# Virtual_Boy.net
KiCad netlist of a schematic drawn in EAGLE
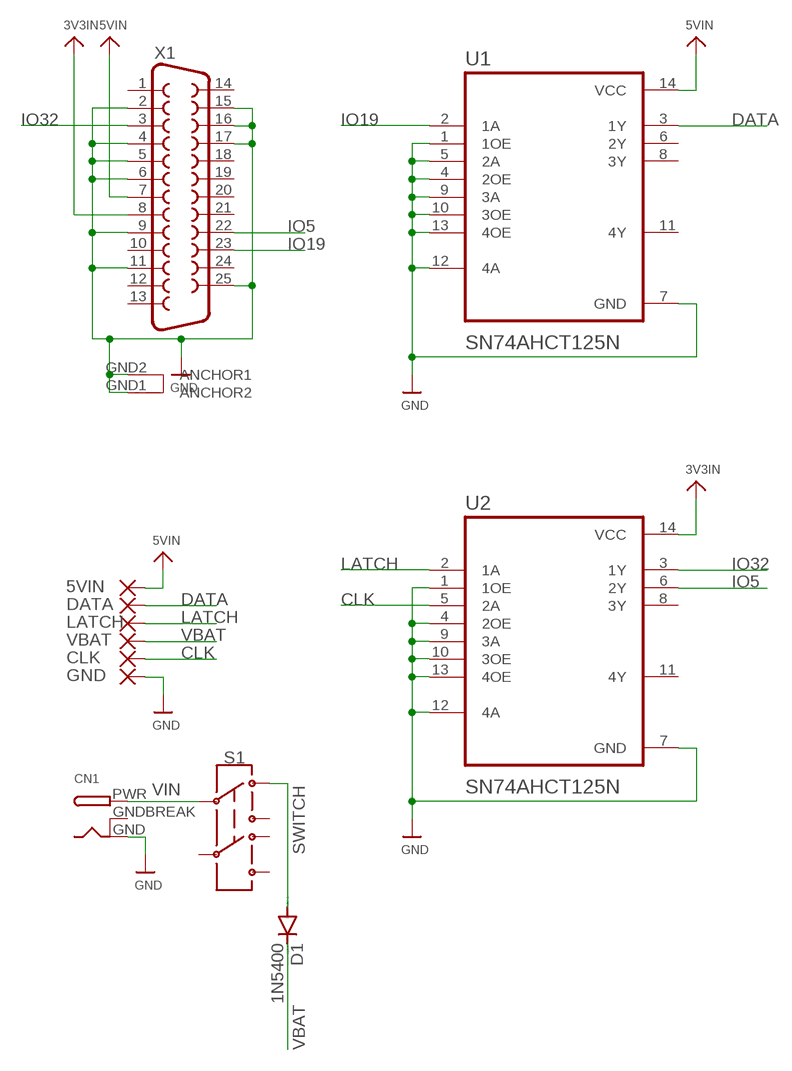
[diagram p0: schematic, sheet 1]

(export (version "E")
  (design (tool "Eeschema 10.0.6"))
  (components
    (comp (ref "5VIN")
      (value "SMD5")
      (footprint "eagle-import:SMD2,54-5,08")
      (libsource (lib "eagle-import") (part "SMD5"))
    )
    (comp (ref "CLK")
      (value "SMD5")
      (footprint "eagle-import:SMD2,54-5,08")
      (libsource (lib "eagle-import") (part "SMD5"))
    )
    (comp (ref "CN1")
      (value "DCBARRELPTH")
      (footprint "eagle-import:DCJACK_2MM_PTH")
      (libsource (lib "eagle-import") (part "DCBARRELPTH"))
    )
    (comp (ref "D1")
      (value "1N5400")
      (footprint "eagle-import:DO201-15")
      (libsource (lib "eagle-import") (part "1N5400"))
    )
    (comp (ref "DATA")
      (value "SMD5")
      (footprint "eagle-import:SMD2,54-5,08")
      (libsource (lib "eagle-import") (part "SMD5"))
    )
    (comp (ref "GND")
      (value "SMD5")
      (footprint "eagle-import:SMD2,54-5,08")
      (libsource (lib "eagle-import") (part "SMD5"))
    )
    (comp (ref "LATCH")
      (value "SMD5")
      (footprint "eagle-import:SMD2,54-5,08")
      (libsource (lib "eagle-import") (part "SMD5"))
    )
    (comp (ref "S1")
      (value "SWITCH-DPDT-PTH-GPI-152-3013")
      (footprint "eagle-import:SWITCH_DPDT_PTH_GPI-152-3013")
      (libsource (lib "eagle-import") (part "SWITCH-DPDT-PTH-GPI-152-3013"))
    )
    (comp (ref "U1")
      (value "SN74AHCT125N")
      (footprint "eagle-import:DIP794W45P254L1969H508Q14")
      (fields (field (name "MF") "Texas Instruments"))
      (libsource (lib "eagle-import") (part "SN74AHCT125N"))
    )
    (comp (ref "U2")
      (value "SN74AHCT125N")
      (footprint "eagle-import:DIP794W45P254L1969H508Q14")
      (fields (field (name "MF") "Texas Instruments"))
      (libsource (lib "eagle-import") (part "SN74AHCT125N"))
    )
    (comp (ref "VBAT")
      (value "SMD5")
      (footprint "eagle-import:SMD2,54-5,08")
      (libsource (lib "eagle-import") (part "SMD5"))
    )
    (comp (ref "X1")
      (value "DB25_FEMALEHP")
      (footprint "eagle-import:F25HP")
      (libsource (lib "eagle-import") (part "DB25_FEMALEHP"))
    )
  )
  (nets
    (net (code "1") (name "/CLK") (class "Default")
      (node (ref "CLK") (pin "1") (pinfunction "P_1") (pintype "passive"))
      (node (ref "U2") (pin "5") (pinfunction "2A_5") (pintype "input"))
    )
    (net (code "2") (name "/DATA") (class "Default")
      (node (ref "DATA") (pin "1") (pinfunction "P_1") (pintype "passive"))
      (node (ref "U1") (pin "3") (pinfunction "1Y_3") (pintype "output"))
    )
    (net (code "3") (name "/GNDBREAK") (class "Default")
      (node (ref "CN1") (pin "GNDBREAK") (pinfunction "GNDBREAK_GNDBREAK") (pintype "power_in"))
    )
    (net (code "4") (name "/IO5") (class "Default")
      (node (ref "U2") (pin "6") (pinfunction "2Y_6") (pintype "output"))
      (node (ref "X1") (pin "22") (pinfunction "22_22") (pintype "passive"))
    )
    (net (code "5") (name "/IO19") (class "Default")
      (node (ref "U1") (pin "2") (pinfunction "1A_2") (pintype "input"))
      (node (ref "X1") (pin "23") (pinfunction "23_23") (pintype "passive"))
    )
    (net (code "6") (name "/IO32") (class "Default")
      (node (ref "U2") (pin "3") (pinfunction "1Y_3") (pintype "output"))
      (node (ref "X1") (pin "3") (pinfunction "3_3") (pintype "passive"))
    )
    (net (code "7") (name "/LATCH") (class "Default")
      (node (ref "LATCH") (pin "1") (pinfunction "P_1") (pintype "passive"))
      (node (ref "U2") (pin "2") (pinfunction "1A_2") (pintype "input"))
    )
    (net (code "8") (name "/SWITCH") (class "Default")
      (node (ref "D1") (pin "A") (pinfunction "A_A") (pintype "passive"))
      (node (ref "S1") (pin "10") (pinfunction "1_10") (pintype "bidirectional"))
    )
    (net (code "9") (name "/VBAT") (class "Default")
      (node (ref "D1") (pin "C") (pinfunction "C_C") (pintype "passive"))
      (node (ref "VBAT") (pin "1") (pinfunction "P_1") (pintype "passive"))
    )
    (net (code "10") (name "/VIN") (class "Default")
      (node (ref "CN1") (pin "PWR") (pinfunction "PWR_PWR") (pintype "power_in"))
      (node (ref "S1") (pin "C@1") (pinfunction "2_C@1") (pintype "bidirectional"))
    )
    (net (code "11") (name "3V3IN") (class "Default")
      (node (ref "U2") (pin "14") (pinfunction "VCC_14") (pintype "power_in"))
      (node (ref "X1") (pin "8") (pinfunction "8_8") (pintype "passive"))
    )
    (net (code "12") (name "5VIN") (class "Default")
      (node (ref "5VIN") (pin "1") (pinfunction "P_1") (pintype "passive"))
      (node (ref "U1") (pin "14") (pinfunction "VCC_14") (pintype "power_in"))
      (node (ref "X1") (pin "7") (pinfunction "7_7") (pintype "passive"))
    )
    (net (code "13") (name "GND") (class "Default")
      (node (ref "CN1") (pin "GND") (pinfunction "GND_GND") (pintype "power_in"))
      (node (ref "GND") (pin "1") (pinfunction "P_1") (pintype "passive"))
      (node (ref "U1") (pin "1") (pinfunction "1OE_1") (pintype "input"))
      (node (ref "U1") (pin "10") (pinfunction "3OE_10") (pintype "input"))
      (node (ref "U1") (pin "12") (pinfunction "4A_12") (pintype "bidirectional"))
      (node (ref "U1") (pin "13") (pinfunction "4OE_13") (pintype "input"))
      (node (ref "U1") (pin "4") (pinfunction "2OE_4") (pintype "input"))
      (node (ref "U1") (pin "5") (pinfunction "2A_5") (pintype "input"))
      (node (ref "U1") (pin "7") (pinfunction "GND_7") (pintype "power_in"))
      (node (ref "U1") (pin "9") (pinfunction "3A_9") (pintype "input"))
      (node (ref "U2") (pin "1") (pinfunction "1OE_1") (pintype "input"))
      (node (ref "U2") (pin "10") (pinfunction "3OE_10") (pintype "input"))
      (node (ref "U2") (pin "12") (pinfunction "4A_12") (pintype "bidirectional"))
      (node (ref "U2") (pin "13") (pinfunction "4OE_13") (pintype "input"))
      (node (ref "U2") (pin "4") (pinfunction "2OE_4") (pintype "input"))
      (node (ref "U2") (pin "7") (pinfunction "GND_7") (pintype "power_in"))
      (node (ref "U2") (pin "9") (pinfunction "3A_9") (pintype "input"))
      (node (ref "X1") (pin "11") (pinfunction "11_11") (pintype "passive"))
      (node (ref "X1") (pin "15") (pinfunction "15_15") (pintype "passive"))
      (node (ref "X1") (pin "16") (pinfunction "16_16") (pintype "passive"))
      (node (ref "X1") (pin "17") (pinfunction "17_17") (pintype "passive"))
      (node (ref "X1") (pin "2") (pinfunction "2_2") (pintype "passive"))
      (node (ref "X1") (pin "25") (pinfunction "25_25") (pintype "passive"))
      (node (ref "X1") (pin "4") (pinfunction "4_4") (pintype "passive"))
      (node (ref "X1") (pin "5") (pinfunction "5_5") (pintype "passive"))
      (node (ref "X1") (pin "6") (pinfunction "6_6") (pintype "passive"))
      (node (ref "X1") (pin "9") (pinfunction "9_9") (pintype "passive"))
      (node (ref "X1") (pin "GND1") (pinfunction "ANCHOR2_GND1") (pintype "bidirectional"))
      (node (ref "X1") (pin "GND2") (pinfunction "ANCHOR1_GND2") (pintype "bidirectional"))
    )
    (net (code "14") (name "unconnected-(S1-3-Pad20)") (class "Default")
      (node (ref "S1") (pin "20") (pinfunction "3_20") (pintype "bidirectional"))
    )
    (net (code "15") (name "unconnected-(S1-4-Pad11)") (class "Default")
      (node (ref "S1") (pin "11") (pinfunction "4_11") (pintype "bidirectional"))
    )
    (net (code "16") (name "unconnected-(S1-5-PadC@2)") (class "Default")
      (node (ref "S1") (pin "C@2") (pinfunction "5_C@2") (pintype "bidirectional"))
    )
    (net (code "17") (name "unconnected-(S1-6-Pad21)") (class "Default")
      (node (ref "S1") (pin "21") (pinfunction "6_21") (pintype "bidirectional"))
    )
    (net (code "18") (name "unconnected-(U1-2Y-Pad6)") (class "Default")
      (node (ref "U1") (pin "6") (pinfunction "2Y_6") (pintype "output"))
    )
    (net (code "19") (name "unconnected-(U1-3Y-Pad8)") (class "Default")
      (node (ref "U1") (pin "8") (pinfunction "3Y_8") (pintype "output"))
    )
    (net (code "20") (name "unconnected-(U1-4Y-Pad11)") (class "Default")
      (node (ref "U1") (pin "11") (pinfunction "4Y_11") (pintype "output"))
    )
    (net (code "21") (name "unconnected-(U2-3Y-Pad8)") (class "Default")
      (node (ref "U2") (pin "8") (pinfunction "3Y_8") (pintype "output"))
    )
    (net (code "22") (name "unconnected-(U2-4Y-Pad11)") (class "Default")
      (node (ref "U2") (pin "11") (pinfunction "4Y_11") (pintype "output"))
    )
    (net (code "23") (name "unconnected-(X1-Pad1)") (class "Default")
      (node (ref "X1") (pin "1") (pinfunction "1_1") (pintype "passive"))
    )
    (net (code "24") (name "unconnected-(X1-Pad10)") (class "Default")
      (node (ref "X1") (pin "10") (pinfunction "10_10") (pintype "passive"))
    )
    (net (code "25") (name "unconnected-(X1-Pad12)") (class "Default")
      (node (ref "X1") (pin "12") (pinfunction "12_12") (pintype "passive"))
    )
    (net (code "26") (name "unconnected-(X1-Pad13)") (class "Default")
      (node (ref "X1") (pin "13") (pinfunction "13_13") (pintype "passive"))
    )
    (net (code "27") (name "unconnected-(X1-Pad14)") (class "Default")
      (node (ref "X1") (pin "14") (pinfunction "14_14") (pintype "passive"))
    )
    (net (code "28") (name "unconnected-(X1-Pad18)") (class "Default")
      (node (ref "X1") (pin "18") (pinfunction "18_18") (pintype "passive"))
    )
    (net (code "29") (name "unconnected-(X1-Pad19)") (class "Default")
      (node (ref "X1") (pin "19") (pinfunction "19_19") (pintype "passive"))
    )
    (net (code "30") (name "unconnected-(X1-Pad20)") (class "Default")
      (node (ref "X1") (pin "20") (pinfunction "20_20") (pintype "passive"))
    )
    (net (code "31") (name "unconnected-(X1-Pad21)") (class "Default")
      (node (ref "X1") (pin "21") (pinfunction "21_21") (pintype "passive"))
    )
    (net (code "32") (name "unconnected-(X1-Pad24)") (class "Default")
      (node (ref "X1") (pin "24") (pinfunction "24_24") (pintype "passive"))
    )
  )
)
